# RLC.net
KiCad netlist of a schematic drawn in EAGLE
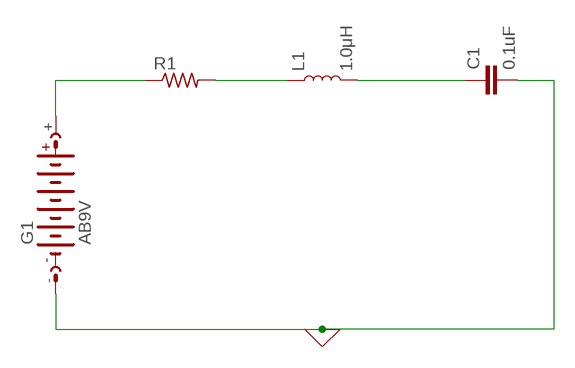
[diagram p0: schematic, sheet 1]

(export (version "E")
  (design (tool "Eeschema 10.0.6"))
  (components
    (comp (ref "C1")
      (value "0.1uF")
      (footprint "eagle-import:0402")
      (libsource (lib "eagle-import") (part "0.1UF-0402-6.3V-10%-X7R"))
    )
    (comp (ref "G1")
      (value "AB9V")
      (footprint "eagle-import:AB9V")
      (libsource (lib "eagle-import") (part "AB9V"))
    )
    (comp (ref "L1")
      (value "1.0μH")
      (footprint "eagle-import:0805-WIDE")
      (libsource (lib "eagle-import") (part "1.0μH-0805_WIDE-1.0μH-1.4A-0.07OHM-1.4MM_H"))
    )
    (comp (ref "R1")
      (value "R-US_0204/2V")
      (footprint "eagle-import:0204V")
      (libsource (lib "eagle-import") (part "R-US_0204/2V"))
    )
  )
  (nets
    (net (code "1") (name "GND") (class "Default")
      (node (ref "C1") (pin "2") (pinfunction "2_2") (pintype "passive"))
      (node (ref "G1") (pin "-") (pinfunction "-_-") (pintype "passive"))
    )
    (net (code "2") (name "Net-(C1-Pad1)") (class "Default")
      (node (ref "C1") (pin "1") (pinfunction "1_1") (pintype "passive"))
      (node (ref "L1") (pin "2") (pinfunction "2_2") (pintype "passive"))
    )
    (net (code "3") (name "Net-(G1-Pad+)") (class "Default")
      (node (ref "G1") (pin "+") (pinfunction "+_+") (pintype "passive"))
      (node (ref "R1") (pin "1") (pinfunction "1_1") (pintype "passive"))
    )
    (net (code "4") (name "Net-(L1-Pad1)") (class "Default")
      (node (ref "L1") (pin "1") (pinfunction "1_1") (pintype "passive"))
      (node (ref "R1") (pin "2") (pinfunction "2_2") (pintype "passive"))
    )
  )
)
